# ARC_Power_v0_1.net
KiCad netlist of a schematic drawn in EAGLE
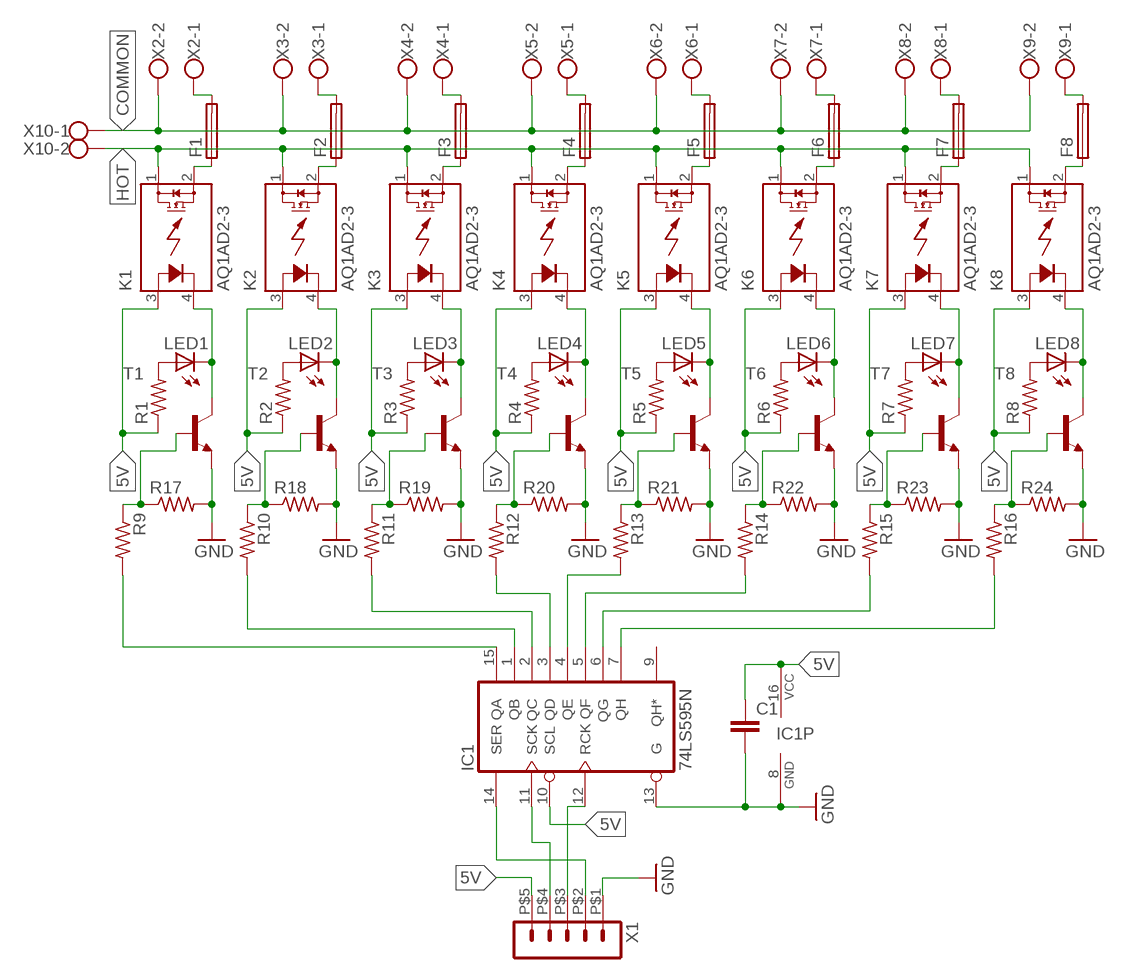
[diagram p0: schematic, sheet 1]

(export (version "E")
  (design (tool "Eeschema 10.0.6"))
  (components
    (comp (ref "C1")
      (value "C5/3")
      (footprint "eagle-import:C5B3")
      (libsource (lib "eagle-import") (part "C5/3"))
    )
    (comp (ref "F1")
      (value "SH22,5A")
      (footprint "eagle-import:SH22,5A")
      (fields (field (name "MPN") "0031.7701.11"))
      (libsource (lib "eagle-import") (part "SH22,5A"))
    )
    (comp (ref "F2")
      (value "SH22,5A")
      (footprint "eagle-import:SH22,5A")
      (fields (field (name "MPN") "0031.7701.11"))
      (libsource (lib "eagle-import") (part "SH22,5A"))
    )
    (comp (ref "F3")
      (value "SH22,5A")
      (footprint "eagle-import:SH22,5A")
      (fields (field (name "MPN") "0031.7701.11"))
      (libsource (lib "eagle-import") (part "SH22,5A"))
    )
    (comp (ref "F4")
      (value "SH22,5A")
      (footprint "eagle-import:SH22,5A")
      (fields (field (name "MPN") "0031.7701.11"))
      (libsource (lib "eagle-import") (part "SH22,5A"))
    )
    (comp (ref "F5")
      (value "SH22,5A")
      (footprint "eagle-import:SH22,5A")
      (fields (field (name "MPN") "0031.7701.11"))
      (libsource (lib "eagle-import") (part "SH22,5A"))
    )
    (comp (ref "F6")
      (value "SH22,5A")
      (footprint "eagle-import:SH22,5A")
      (fields (field (name "MPN") "0031.7701.11"))
      (libsource (lib "eagle-import") (part "SH22,5A"))
    )
    (comp (ref "F7")
      (value "SH22,5A")
      (footprint "eagle-import:SH22,5A")
      (fields (field (name "MPN") "0031.7701.11"))
      (libsource (lib "eagle-import") (part "SH22,5A"))
    )
    (comp (ref "F8")
      (value "SH22,5A")
      (footprint "eagle-import:SH22,5A")
      (fields (field (name "MPN") "0031.7701.11"))
      (libsource (lib "eagle-import") (part "SH22,5A"))
    )
    (comp (ref "IC1")
      (value "74LS595N")
      (footprint "eagle-import:DIL16")
      (libsource (lib "eagle-import") (part "74595NLS"))
    )
    (comp (ref "K1")
      (value "AQ1AD2-3")
      (footprint "eagle-import:AQ1")
      (fields (field (name "MF") "AROMAT/ MATSUSHITA") (field (name "MPN") "AQ1AD2-3/28VDC"))
      (libsource (lib "eagle-import") (part "AQ1AD2-3"))
    )
    (comp (ref "K2")
      (value "AQ1AD2-3")
      (footprint "eagle-import:AQ1")
      (fields (field (name "MF") "AROMAT/ MATSUSHITA") (field (name "MPN") "AQ1AD2-3/28VDC"))
      (libsource (lib "eagle-import") (part "AQ1AD2-3"))
    )
    (comp (ref "K3")
      (value "AQ1AD2-3")
      (footprint "eagle-import:AQ1")
      (fields (field (name "MF") "AROMAT/ MATSUSHITA") (field (name "MPN") "AQ1AD2-3/28VDC"))
      (libsource (lib "eagle-import") (part "AQ1AD2-3"))
    )
    (comp (ref "K4")
      (value "AQ1AD2-3")
      (footprint "eagle-import:AQ1")
      (fields (field (name "MF") "AROMAT/ MATSUSHITA") (field (name "MPN") "AQ1AD2-3/28VDC"))
      (libsource (lib "eagle-import") (part "AQ1AD2-3"))
    )
    (comp (ref "K5")
      (value "AQ1AD2-3")
      (footprint "eagle-import:AQ1")
      (fields (field (name "MF") "AROMAT/ MATSUSHITA") (field (name "MPN") "AQ1AD2-3/28VDC"))
      (libsource (lib "eagle-import") (part "AQ1AD2-3"))
    )
    (comp (ref "K6")
      (value "AQ1AD2-3")
      (footprint "eagle-import:AQ1")
      (fields (field (name "MF") "AROMAT/ MATSUSHITA") (field (name "MPN") "AQ1AD2-3/28VDC"))
      (libsource (lib "eagle-import") (part "AQ1AD2-3"))
    )
    (comp (ref "K7")
      (value "AQ1AD2-3")
      (footprint "eagle-import:AQ1")
      (fields (field (name "MF") "AROMAT/ MATSUSHITA") (field (name "MPN") "AQ1AD2-3/28VDC"))
      (libsource (lib "eagle-import") (part "AQ1AD2-3"))
    )
    (comp (ref "K8")
      (value "AQ1AD2-3")
      (footprint "eagle-import:AQ1")
      (fields (field (name "MF") "AROMAT/ MATSUSHITA") (field (name "MPN") "AQ1AD2-3/28VDC"))
      (libsource (lib "eagle-import") (part "AQ1AD2-3"))
    )
    (comp (ref "LED1")
      (value "LED3MM")
      (footprint "eagle-import:LED3MM")
      (libsource (lib "eagle-import") (part "LED3MM"))
    )
    (comp (ref "LED2")
      (value "LED3MM")
      (footprint "eagle-import:LED3MM")
      (libsource (lib "eagle-import") (part "LED3MM"))
    )
    (comp (ref "LED3")
      (value "LED3MM")
      (footprint "eagle-import:LED3MM")
      (libsource (lib "eagle-import") (part "LED3MM"))
    )
    (comp (ref "LED4")
      (value "LED3MM")
      (footprint "eagle-import:LED3MM")
      (libsource (lib "eagle-import") (part "LED3MM"))
    )
    (comp (ref "LED5")
      (value "LED3MM")
      (footprint "eagle-import:LED3MM")
      (libsource (lib "eagle-import") (part "LED3MM"))
    )
    (comp (ref "LED6")
      (value "LED3MM")
      (footprint "eagle-import:LED3MM")
      (libsource (lib "eagle-import") (part "LED3MM"))
    )
    (comp (ref "LED7")
      (value "LED3MM")
      (footprint "eagle-import:LED3MM")
      (libsource (lib "eagle-import") (part "LED3MM"))
    )
    (comp (ref "LED8")
      (value "LED3MM")
      (footprint "eagle-import:LED3MM")
      (libsource (lib "eagle-import") (part "LED3MM"))
    )
    (comp (ref "R1")
      (value "R-US_0204/7")
      (footprint "eagle-import:0204_7")
      (libsource (lib "eagle-import") (part "R-US_0204/7"))
    )
    (comp (ref "R2")
      (value "R-US_0204/7")
      (footprint "eagle-import:0204_7")
      (libsource (lib "eagle-import") (part "R-US_0204/7"))
    )
    (comp (ref "R3")
      (value "R-US_0204/7")
      (footprint "eagle-import:0204_7")
      (libsource (lib "eagle-import") (part "R-US_0204/7"))
    )
    (comp (ref "R4")
      (value "R-US_0204/7")
      (footprint "eagle-import:0204_7")
      (libsource (lib "eagle-import") (part "R-US_0204/7"))
    )
    (comp (ref "R5")
      (value "R-US_0204/7")
      (footprint "eagle-import:0204_7")
      (libsource (lib "eagle-import") (part "R-US_0204/7"))
    )
    (comp (ref "R6")
      (value "R-US_0204/7")
      (footprint "eagle-import:0204_7")
      (libsource (lib "eagle-import") (part "R-US_0204/7"))
    )
    (comp (ref "R7")
      (value "R-US_0204/7")
      (footprint "eagle-import:0204_7")
      (libsource (lib "eagle-import") (part "R-US_0204/7"))
    )
    (comp (ref "R8")
      (value "R-US_0204/7")
      (footprint "eagle-import:0204_7")
      (libsource (lib "eagle-import") (part "R-US_0204/7"))
    )
    (comp (ref "R9")
      (value "R-US_0204/7")
      (footprint "eagle-import:0204_7")
      (libsource (lib "eagle-import") (part "R-US_0204/7"))
    )
    (comp (ref "R10")
      (value "R-US_0204/7")
      (footprint "eagle-import:0204_7")
      (libsource (lib "eagle-import") (part "R-US_0204/7"))
    )
    (comp (ref "R11")
      (value "R-US_0204/7")
      (footprint "eagle-import:0204_7")
      (libsource (lib "eagle-import") (part "R-US_0204/7"))
    )
    (comp (ref "R12")
      (value "R-US_0204/7")
      (footprint "eagle-import:0204_7")
      (libsource (lib "eagle-import") (part "R-US_0204/7"))
    )
    (comp (ref "R13")
      (value "R-US_0204/7")
      (footprint "eagle-import:0204_7")
      (libsource (lib "eagle-import") (part "R-US_0204/7"))
    )
    (comp (ref "R14")
      (value "R-US_0204/7")
      (footprint "eagle-import:0204_7")
      (libsource (lib "eagle-import") (part "R-US_0204/7"))
    )
    (comp (ref "R15")
      (value "R-US_0204/7")
      (footprint "eagle-import:0204_7")
      (libsource (lib "eagle-import") (part "R-US_0204/7"))
    )
    (comp (ref "R16")
      (value "R-US_0204/7")
      (footprint "eagle-import:0204_7")
      (libsource (lib "eagle-import") (part "R-US_0204/7"))
    )
    (comp (ref "R17")
      (value "R-US_0204/7")
      (footprint "eagle-import:0204_7")
      (libsource (lib "eagle-import") (part "R-US_0204/7"))
    )
    (comp (ref "R18")
      (value "R-US_0204/7")
      (footprint "eagle-import:0204_7")
      (libsource (lib "eagle-import") (part "R-US_0204/7"))
    )
    (comp (ref "R19")
      (value "R-US_0204/7")
      (footprint "eagle-import:0204_7")
      (libsource (lib "eagle-import") (part "R-US_0204/7"))
    )
    (comp (ref "R20")
      (value "R-US_0204/7")
      (footprint "eagle-import:0204_7")
      (libsource (lib "eagle-import") (part "R-US_0204/7"))
    )
    (comp (ref "R21")
      (value "R-US_0204/7")
      (footprint "eagle-import:0204_7")
      (libsource (lib "eagle-import") (part "R-US_0204/7"))
    )
    (comp (ref "R22")
      (value "R-US_0204/7")
      (footprint "eagle-import:0204_7")
      (libsource (lib "eagle-import") (part "R-US_0204/7"))
    )
    (comp (ref "R23")
      (value "R-US_0204/7")
      (footprint "eagle-import:0204_7")
      (libsource (lib "eagle-import") (part "R-US_0204/7"))
    )
    (comp (ref "R24")
      (value "R-US_0204/7")
      (footprint "eagle-import:0204_7")
      (libsource (lib "eagle-import") (part "R-US_0204/7"))
    )
    (comp (ref "T1")
      (value "-NPN-TO92")
      (footprint "eagle-import:TO92")
      (libsource (lib "eagle-import") (part "-NPN-TO92"))
    )
    (comp (ref "T2")
      (value "-NPN-TO92")
      (footprint "eagle-import:TO92")
      (libsource (lib "eagle-import") (part "-NPN-TO92"))
    )
    (comp (ref "T3")
      (value "-NPN-TO92")
      (footprint "eagle-import:TO92")
      (libsource (lib "eagle-import") (part "-NPN-TO92"))
    )
    (comp (ref "T4")
      (value "-NPN-TO92")
      (footprint "eagle-import:TO92")
      (libsource (lib "eagle-import") (part "-NPN-TO92"))
    )
    (comp (ref "T5")
      (value "-NPN-TO92")
      (footprint "eagle-import:TO92")
      (libsource (lib "eagle-import") (part "-NPN-TO92"))
    )
    (comp (ref "T6")
      (value "-NPN-TO92")
      (footprint "eagle-import:TO92")
      (libsource (lib "eagle-import") (part "-NPN-TO92"))
    )
    (comp (ref "T7")
      (value "-NPN-TO92")
      (footprint "eagle-import:TO92")
      (libsource (lib "eagle-import") (part "-NPN-TO92"))
    )
    (comp (ref "T8")
      (value "-NPN-TO92")
      (footprint "eagle-import:TO92")
      (libsource (lib "eagle-import") (part "-NPN-TO92"))
    )
    (comp (ref "X1")
      (value "HEADER_POS5_43650-0500")
      (footprint "eagle-import:43650-0500")
      (libsource (lib "eagle-import") (part "HEADER_POS5_?43650-0500"))
    )
    (comp (ref "X2")
      (value "W237-113")
      (footprint "eagle-import:W237-113")
      (libsource (lib "eagle-import") (part "W237-113"))
    )
    (comp (ref "X3")
      (value "W237-113")
      (footprint "eagle-import:W237-113")
      (libsource (lib "eagle-import") (part "W237-113"))
    )
    (comp (ref "X4")
      (value "W237-113")
      (footprint "eagle-import:W237-113")
      (libsource (lib "eagle-import") (part "W237-113"))
    )
    (comp (ref "X5")
      (value "W237-113")
      (footprint "eagle-import:W237-113")
      (libsource (lib "eagle-import") (part "W237-113"))
    )
    (comp (ref "X6")
      (value "W237-113")
      (footprint "eagle-import:W237-113")
      (libsource (lib "eagle-import") (part "W237-113"))
    )
    (comp (ref "X7")
      (value "W237-113")
      (footprint "eagle-import:W237-113")
      (libsource (lib "eagle-import") (part "W237-113"))
    )
    (comp (ref "X8")
      (value "W237-113")
      (footprint "eagle-import:W237-113")
      (libsource (lib "eagle-import") (part "W237-113"))
    )
    (comp (ref "X9")
      (value "W237-113")
      (footprint "eagle-import:W237-113")
      (libsource (lib "eagle-import") (part "W237-113"))
    )
    (comp (ref "X10")
      (value "W237-102")
      (footprint "eagle-import:W237-102")
      (fields (field (name "MPN") "237-102"))
      (libsource (lib "eagle-import") (part "W237-102"))
    )
  )
  (nets
    (net (code "1") (name "5V") (class "Default")
      (node (ref "C1") (pin "1") (pinfunction "1_1") (pintype "passive"))
      (node (ref "IC1") (pin "10") (pinfunction "SCL_10") (pintype "input"))
      (node (ref "IC1") (pin "16") (pinfunction "VCC_16") (pintype "power_in"))
      (node (ref "K1") (pin "3") (pinfunction "A_3") (pintype "passive"))
      (node (ref "K2") (pin "3") (pinfunction "A_3") (pintype "passive"))
      (node (ref "K3") (pin "3") (pinfunction "A_3") (pintype "passive"))
      (node (ref "K4") (pin "3") (pinfunction "A_3") (pintype "passive"))
      (node (ref "K5") (pin "3") (pinfunction "A_3") (pintype "passive"))
      (node (ref "K6") (pin "3") (pinfunction "A_3") (pintype "passive"))
      (node (ref "K7") (pin "3") (pinfunction "A_3") (pintype "passive"))
      (node (ref "K8") (pin "3") (pinfunction "A_3") (pintype "passive"))
      (node (ref "R1") (pin "1") (pinfunction "1_1") (pintype "passive"))
      (node (ref "R2") (pin "1") (pinfunction "1_1") (pintype "passive"))
      (node (ref "R3") (pin "1") (pinfunction "1_1") (pintype "passive"))
      (node (ref "R4") (pin "1") (pinfunction "1_1") (pintype "passive"))
      (node (ref "R5") (pin "1") (pinfunction "1_1") (pintype "passive"))
      (node (ref "R6") (pin "1") (pinfunction "1_1") (pintype "passive"))
      (node (ref "R7") (pin "1") (pinfunction "1_1") (pintype "passive"))
      (node (ref "R8") (pin "1") (pinfunction "1_1") (pintype "passive"))
      (node (ref "X1") (pin "P$5") (pinfunction "5_P$5") (pintype "passive"))
    )
    (net (code "2") (name "COMMON") (class "Default")
      (node (ref "X10") (pin "1") (pinfunction "KL_1") (pintype "passive"))
      (node (ref "X2") (pin "2") (pinfunction "KL_2") (pintype "passive"))
      (node (ref "X3") (pin "2") (pinfunction "KL_2") (pintype "passive"))
      (node (ref "X4") (pin "2") (pinfunction "KL_2") (pintype "passive"))
      (node (ref "X5") (pin "2") (pinfunction "KL_2") (pintype "passive"))
      (node (ref "X6") (pin "2") (pinfunction "KL_2") (pintype "passive"))
      (node (ref "X7") (pin "2") (pinfunction "KL_2") (pintype "passive"))
      (node (ref "X8") (pin "2") (pinfunction "KL_2") (pintype "passive"))
      (node (ref "X9") (pin "2") (pinfunction "KL_2") (pintype "passive"))
    )
    (net (code "3") (name "GND") (class "Default")
      (node (ref "C1") (pin "2") (pinfunction "2_2") (pintype "passive"))
      (node (ref "IC1") (pin "13") (pinfunction "G_13") (pintype "input"))
      (node (ref "IC1") (pin "8") (pinfunction "GND_8") (pintype "power_in"))
      (node (ref "R17") (pin "2") (pinfunction "2_2") (pintype "passive"))
      (node (ref "R18") (pin "2") (pinfunction "2_2") (pintype "passive"))
      (node (ref "R19") (pin "2") (pinfunction "2_2") (pintype "passive"))
      (node (ref "R20") (pin "2") (pinfunction "2_2") (pintype "passive"))
      (node (ref "R21") (pin "2") (pinfunction "2_2") (pintype "passive"))
      (node (ref "R22") (pin "2") (pinfunction "2_2") (pintype "passive"))
      (node (ref "R23") (pin "2") (pinfunction "2_2") (pintype "passive"))
      (node (ref "R24") (pin "2") (pinfunction "2_2") (pintype "passive"))
      (node (ref "T1") (pin "1") (pinfunction "E_1") (pintype "passive"))
      (node (ref "T2") (pin "1") (pinfunction "E_1") (pintype "passive"))
      (node (ref "T3") (pin "1") (pinfunction "E_1") (pintype "passive"))
      (node (ref "T4") (pin "1") (pinfunction "E_1") (pintype "passive"))
      (node (ref "T5") (pin "1") (pinfunction "E_1") (pintype "passive"))
      (node (ref "T6") (pin "1") (pinfunction "E_1") (pintype "passive"))
      (node (ref "T7") (pin "1") (pinfunction "E_1") (pintype "passive"))
      (node (ref "T8") (pin "1") (pinfunction "E_1") (pintype "passive"))
      (node (ref "X1") (pin "P$1") (pinfunction "1_P$1") (pintype "passive"))
    )
    (net (code "4") (name "HOT") (class "Default")
      (node (ref "K1") (pin "1") (pinfunction "DS1_1") (pintype "passive"))
      (node (ref "K2") (pin "1") (pinfunction "DS1_1") (pintype "passive"))
      (node (ref "K3") (pin "1") (pinfunction "DS1_1") (pintype "passive"))
      (node (ref "K4") (pin "1") (pinfunction "DS1_1") (pintype "passive"))
      (node (ref "K5") (pin "1") (pinfunction "DS1_1") (pintype "passive"))
      (node (ref "K6") (pin "1") (pinfunction "DS1_1") (pintype "passive"))
      (node (ref "K7") (pin "1") (pinfunction "DS1_1") (pintype "passive"))
      (node (ref "K8") (pin "1") (pinfunction "DS1_1") (pintype "passive"))
      (node (ref "X10") (pin "2") (pinfunction "KL_2") (pintype "passive"))
    )
    (net (code "5") (name "Net-(IC1A-QA)") (class "Default")
      (node (ref "IC1") (pin "15") (pinfunction "QA_15") (pintype "tri_state"))
      (node (ref "R9") (pin "2") (pinfunction "2_2") (pintype "passive"))
    )
    (net (code "6") (name "Net-(IC1A-QB)") (class "Default")
      (node (ref "IC1") (pin "1") (pinfunction "QB_1") (pintype "tri_state"))
      (node (ref "R10") (pin "2") (pinfunction "2_2") (pintype "passive"))
    )
    (net (code "7") (name "Net-(IC1A-QC)") (class "Default")
      (node (ref "IC1") (pin "2") (pinfunction "QC_2") (pintype "tri_state"))
      (node (ref "R11") (pin "2") (pinfunction "2_2") (pintype "passive"))
    )
    (net (code "8") (name "Net-(IC1A-QD)") (class "Default")
      (node (ref "IC1") (pin "3") (pinfunction "QD_3") (pintype "tri_state"))
      (node (ref "R12") (pin "2") (pinfunction "2_2") (pintype "passive"))
    )
    (net (code "9") (name "Net-(IC1A-QE)") (class "Default")
      (node (ref "IC1") (pin "4") (pinfunction "QE_4") (pintype "tri_state"))
      (node (ref "R13") (pin "2") (pinfunction "2_2") (pintype "passive"))
    )
    (net (code "10") (name "Net-(IC1A-QF)") (class "Default")
      (node (ref "IC1") (pin "5") (pinfunction "QF_5") (pintype "tri_state"))
      (node (ref "R14") (pin "2") (pinfunction "2_2") (pintype "passive"))
    )
    (net (code "11") (name "Net-(IC1A-QG)") (class "Default")
      (node (ref "IC1") (pin "6") (pinfunction "QG_6") (pintype "tri_state"))
      (node (ref "R15") (pin "2") (pinfunction "2_2") (pintype "passive"))
    )
    (net (code "12") (name "Net-(IC1A-QH)") (class "Default")
      (node (ref "IC1") (pin "7") (pinfunction "QH_7") (pintype "tri_state"))
      (node (ref "R16") (pin "2") (pinfunction "2_2") (pintype "passive"))
    )
    (net (code "13") (name "Net-(IC1A-RCK)") (class "Default")
      (node (ref "IC1") (pin "12") (pinfunction "RCK_12") (pintype "input"))
      (node (ref "X1") (pin "P$3") (pinfunction "3_P$3") (pintype "passive"))
    )
    (net (code "14") (name "Net-(IC1A-SCK)") (class "Default")
      (node (ref "IC1") (pin "11") (pinfunction "SCK_11") (pintype "input"))
      (node (ref "X1") (pin "P$4") (pinfunction "4_P$4") (pintype "passive"))
    )
    (net (code "15") (name "Net-(IC1A-SER)") (class "Default")
      (node (ref "IC1") (pin "14") (pinfunction "SER_14") (pintype "input"))
      (node (ref "X1") (pin "P$2") (pinfunction "2_P$2") (pintype "passive"))
    )
    (net (code "16") (name "Net-(K1-DS2)") (class "Default")
      (node (ref "F1") (pin "1") (pinfunction "1_1") (pintype "passive"))
      (node (ref "K1") (pin "2") (pinfunction "DS2_2") (pintype "passive"))
    )
    (net (code "17") (name "Net-(K1-K)") (class "Default")
      (node (ref "K1") (pin "4") (pinfunction "K_4") (pintype "passive"))
      (node (ref "LED1") (pin "K") (pinfunction "C_K") (pintype "passive"))
      (node (ref "T1") (pin "3") (pinfunction "C_3") (pintype "passive"))
    )
    (net (code "18") (name "Net-(K2-DS2)") (class "Default")
      (node (ref "F2") (pin "1") (pinfunction "1_1") (pintype "passive"))
      (node (ref "K2") (pin "2") (pinfunction "DS2_2") (pintype "passive"))
    )
    (net (code "19") (name "Net-(K2-K)") (class "Default")
      (node (ref "K2") (pin "4") (pinfunction "K_4") (pintype "passive"))
      (node (ref "LED2") (pin "K") (pinfunction "C_K") (pintype "passive"))
      (node (ref "T2") (pin "3") (pinfunction "C_3") (pintype "passive"))
    )
    (net (code "20") (name "Net-(K3-DS2)") (class "Default")
      (node (ref "F3") (pin "1") (pinfunction "1_1") (pintype "passive"))
      (node (ref "K3") (pin "2") (pinfunction "DS2_2") (pintype "passive"))
    )
    (net (code "21") (name "Net-(K3-K)") (class "Default")
      (node (ref "K3") (pin "4") (pinfunction "K_4") (pintype "passive"))
      (node (ref "LED3") (pin "K") (pinfunction "C_K") (pintype "passive"))
      (node (ref "T3") (pin "3") (pinfunction "C_3") (pintype "passive"))
    )
    (net (code "22") (name "Net-(K4-DS2)") (class "Default")
      (node (ref "F4") (pin "1") (pinfunction "1_1") (pintype "passive"))
      (node (ref "K4") (pin "2") (pinfunction "DS2_2") (pintype "passive"))
    )
    (net (code "23") (name "Net-(K4-K)") (class "Default")
      (node (ref "K4") (pin "4") (pinfunction "K_4") (pintype "passive"))
      (node (ref "LED4") (pin "K") (pinfunction "C_K") (pintype "passive"))
      (node (ref "T4") (pin "3") (pinfunction "C_3") (pintype "passive"))
    )
    (net (code "24") (name "Net-(K5-DS2)") (class "Default")
      (node (ref "F5") (pin "1") (pinfunction "1_1") (pintype "passive"))
      (node (ref "K5") (pin "2") (pinfunction "DS2_2") (pintype "passive"))
    )
    (net (code "25") (name "Net-(K5-K)") (class "Default")
      (node (ref "K5") (pin "4") (pinfunction "K_4") (pintype "passive"))
      (node (ref "LED5") (pin "K") (pinfunction "C_K") (pintype "passive"))
      (node (ref "T5") (pin "3") (pinfunction "C_3") (pintype "passive"))
    )
    (net (code "26") (name "Net-(K6-DS2)") (class "Default")
      (node (ref "F6") (pin "1") (pinfunction "1_1") (pintype "passive"))
      (node (ref "K6") (pin "2") (pinfunction "DS2_2") (pintype "passive"))
    )
    (net (code "27") (name "Net-(K6-K)") (class "Default")
      (node (ref "K6") (pin "4") (pinfunction "K_4") (pintype "passive"))
      (node (ref "LED6") (pin "K") (pinfunction "C_K") (pintype "passive"))
      (node (ref "T6") (pin "3") (pinfunction "C_3") (pintype "passive"))
    )
    (net (code "28") (name "Net-(K7-DS2)") (class "Default")
      (node (ref "F7") (pin "1") (pinfunction "1_1") (pintype "passive"))
      (node (ref "K7") (pin "2") (pinfunction "DS2_2") (pintype "passive"))
    )
    (net (code "29") (name "Net-(K7-K)") (class "Default")
      (node (ref "K7") (pin "4") (pinfunction "K_4") (pintype "passive"))
      (node (ref "LED7") (pin "K") (pinfunction "C_K") (pintype "passive"))
      (node (ref "T7") (pin "3") (pinfunction "C_3") (pintype "passive"))
    )
    (net (code "30") (name "Net-(K8-DS2)") (class "Default")
      (node (ref "F8") (pin "1") (pinfunction "1_1") (pintype "passive"))
      (node (ref "K8") (pin "2") (pinfunction "DS2_2") (pintype "passive"))
    )
    (net (code "31") (name "Net-(K8-K)") (class "Default")
      (node (ref "K8") (pin "4") (pinfunction "K_4") (pintype "passive"))
      (node (ref "LED8") (pin "K") (pinfunction "C_K") (pintype "passive"))
      (node (ref "T8") (pin "3") (pinfunction "C_3") (pintype "passive"))
    )
    (net (code "32") (name "Net-(LED1-PadA)") (class "Default")
      (node (ref "LED1") (pin "A") (pinfunction "A_A") (pintype "passive"))
      (node (ref "R1") (pin "2") (pinfunction "2_2") (pintype "passive"))
    )
    (net (code "33") (name "Net-(LED2-PadA)") (class "Default")
      (node (ref "LED2") (pin "A") (pinfunction "A_A") (pintype "passive"))
      (node (ref "R2") (pin "2") (pinfunction "2_2") (pintype "passive"))
    )
    (net (code "34") (name "Net-(LED3-PadA)") (class "Default")
      (node (ref "LED3") (pin "A") (pinfunction "A_A") (pintype "passive"))
      (node (ref "R3") (pin "2") (pinfunction "2_2") (pintype "passive"))
    )
    (net (code "35") (name "Net-(LED4-PadA)") (class "Default")
      (node (ref "LED4") (pin "A") (pinfunction "A_A") (pintype "passive"))
      (node (ref "R4") (pin "2") (pinfunction "2_2") (pintype "passive"))
    )
    (net (code "36") (name "Net-(LED5-PadA)") (class "Default")
      (node (ref "LED5") (pin "A") (pinfunction "A_A") (pintype "passive"))
      (node (ref "R5") (pin "2") (pinfunction "2_2") (pintype "passive"))
    )
    (net (code "37") (name "Net-(LED6-PadA)") (class "Default")
      (node (ref "LED6") (pin "A") (pinfunction "A_A") (pintype "passive"))
      (node (ref "R6") (pin "2") (pinfunction "2_2") (pintype "passive"))
    )
    (net (code "38") (name "Net-(LED7-PadA)") (class "Default")
      (node (ref "LED7") (pin "A") (pinfunction "A_A") (pintype "passive"))
      (node (ref "R7") (pin "2") (pinfunction "2_2") (pintype "passive"))
    )
    (net (code "39") (name "Net-(LED8-PadA)") (class "Default")
      (node (ref "LED8") (pin "A") (pinfunction "A_A") (pintype "passive"))
      (node (ref "R8") (pin "2") (pinfunction "2_2") (pintype "passive"))
    )
    (net (code "40") (name "Net-(T1-B)") (class "Default")
      (node (ref "R17") (pin "1") (pinfunction "1_1") (pintype "passive"))
      (node (ref "R9") (pin "1") (pinfunction "1_1") (pintype "passive"))
      (node (ref "T1") (pin "2") (pinfunction "B_2") (pintype "passive"))
    )
    (net (code "41") (name "Net-(T2-B)") (class "Default")
      (node (ref "R10") (pin "1") (pinfunction "1_1") (pintype "passive"))
      (node (ref "R18") (pin "1") (pinfunction "1_1") (pintype "passive"))
      (node (ref "T2") (pin "2") (pinfunction "B_2") (pintype "passive"))
    )
    (net (code "42") (name "Net-(T3-B)") (class "Default")
      (node (ref "R11") (pin "1") (pinfunction "1_1") (pintype "passive"))
      (node (ref "R19") (pin "1") (pinfunction "1_1") (pintype "passive"))
      (node (ref "T3") (pin "2") (pinfunction "B_2") (pintype "passive"))
    )
    (net (code "43") (name "Net-(T4-B)") (class "Default")
      (node (ref "R12") (pin "1") (pinfunction "1_1") (pintype "passive"))
      (node (ref "R20") (pin "1") (pinfunction "1_1") (pintype "passive"))
      (node (ref "T4") (pin "2") (pinfunction "B_2") (pintype "passive"))
    )
    (net (code "44") (name "Net-(T5-B)") (class "Default")
      (node (ref "R13") (pin "1") (pinfunction "1_1") (pintype "passive"))
      (node (ref "R21") (pin "1") (pinfunction "1_1") (pintype "passive"))
      (node (ref "T5") (pin "2") (pinfunction "B_2") (pintype "passive"))
    )
    (net (code "45") (name "Net-(T6-B)") (class "Default")
      (node (ref "R14") (pin "1") (pinfunction "1_1") (pintype "passive"))
      (node (ref "R22") (pin "1") (pinfunction "1_1") (pintype "passive"))
      (node (ref "T6") (pin "2") (pinfunction "B_2") (pintype "passive"))
    )
    (net (code "46") (name "Net-(T7-B)") (class "Default")
      (node (ref "R15") (pin "1") (pinfunction "1_1") (pintype "passive"))
      (node (ref "R23") (pin "1") (pinfunction "1_1") (pintype "passive"))
      (node (ref "T7") (pin "2") (pinfunction "B_2") (pintype "passive"))
    )
    (net (code "47") (name "Net-(T8-B)") (class "Default")
      (node (ref "R16") (pin "1") (pinfunction "1_1") (pintype "passive"))
      (node (ref "R24") (pin "1") (pinfunction "1_1") (pintype "passive"))
      (node (ref "T8") (pin "2") (pinfunction "B_2") (pintype "passive"))
    )
    (net (code "48") (name "Net-(X2A-KL)") (class "Default")
      (node (ref "F1") (pin "2") (pinfunction "2_2") (pintype "passive"))
      (node (ref "X2") (pin "1") (pinfunction "KL_1") (pintype "passive"))
    )
    (net (code "49") (name "Net-(X3A-KL)") (class "Default")
      (node (ref "F2") (pin "2") (pinfunction "2_2") (pintype "passive"))
      (node (ref "X3") (pin "1") (pinfunction "KL_1") (pintype "passive"))
    )
    (net (code "50") (name "Net-(X4A-KL)") (class "Default")
      (node (ref "F3") (pin "2") (pinfunction "2_2") (pintype "passive"))
      (node (ref "X4") (pin "1") (pinfunction "KL_1") (pintype "passive"))
    )
    (net (code "51") (name "Net-(X5A-KL)") (class "Default")
      (node (ref "F4") (pin "2") (pinfunction "2_2") (pintype "passive"))
      (node (ref "X5") (pin "1") (pinfunction "KL_1") (pintype "passive"))
    )
    (net (code "52") (name "Net-(X6A-KL)") (class "Default")
      (node (ref "F5") (pin "2") (pinfunction "2_2") (pintype "passive"))
      (node (ref "X6") (pin "1") (pinfunction "KL_1") (pintype "passive"))
    )
    (net (code "53") (name "Net-(X7A-KL)") (class "Default")
      (node (ref "F6") (pin "2") (pinfunction "2_2") (pintype "passive"))
      (node (ref "X7") (pin "1") (pinfunction "KL_1") (pintype "passive"))
    )
    (net (code "54") (name "Net-(X8A-KL)") (class "Default")
      (node (ref "F7") (pin "2") (pinfunction "2_2") (pintype "passive"))
      (node (ref "X8") (pin "1") (pinfunction "KL_1") (pintype "passive"))
    )
    (net (code "55") (name "Net-(X9A-KL)") (class "Default")
      (node (ref "F8") (pin "2") (pinfunction "2_2") (pintype "passive"))
      (node (ref "X9") (pin "1") (pinfunction "KL_1") (pintype "passive"))
    )
    (net (code "56") (name "unconnected-(IC1A-QH*-Pad9)") (class "Default")
      (node (ref "IC1") (pin "9") (pinfunction "QH*_9") (pintype "tri_state"))
    )
  )
)
